# main.net
KiCad netlist of a schematic drawn in Altium Designer
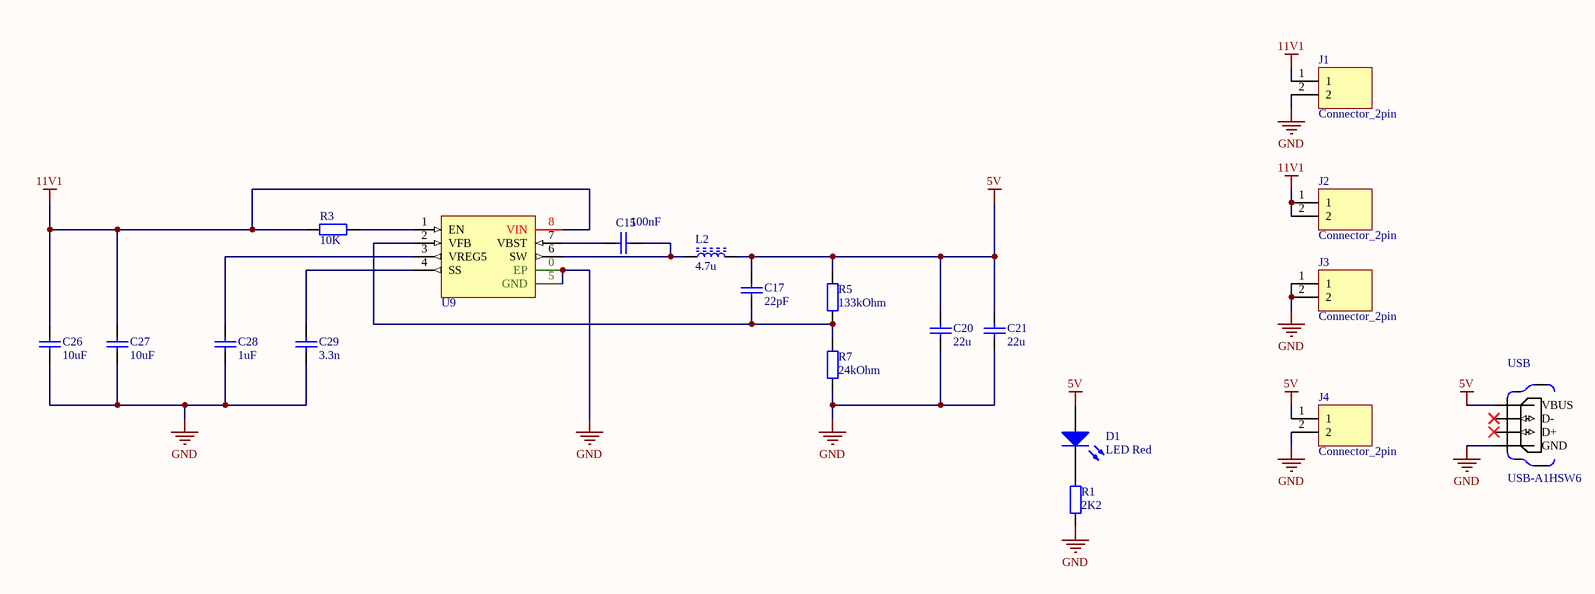
[diagram p0: main.SchDoc]

(export (version "E")
  (design (tool "Eeschema 10.0.6"))
  (components
    (comp (ref "C15")
      (value "100nF")
      (footprint "FP_0805_CAP_085")
      (description "Capacitor")
      (fields (field (name "TOLERANCE") "+80%/-20%") (field (name "VOLTAGE") "25V"))
      (libsource (lib "hallglib") (part "CAP 100nF"))
    )
    (comp (ref "C17")
      (value "22pF")
      (footprint "FP_0805_CAP_085")
      (description "Capacitor")
      (fields (field (name "TOLERANCE") "5%") (field (name "VOLTAGE") "50V"))
      (libsource (lib "hallglib") (part "CAP 22pF"))
    )
    (comp (ref "C20")
      (value "CL32A226KOJNNNE")
      (footprint "1210")
      (description "22uF 1210 10% 16V X5R CL32A226KOJNNNE (SAM) [ 82-08-05 ]")
      (fields (field (name "CAPACITANCE") "22u"))
      (libsource (lib "RobonAUT") (part "CL32A226KOJNNNE"))
    )
    (comp (ref "C21")
      (value "CL32A226KOJNNNE")
      (footprint "1210")
      (description "22uF 1210 10% 16V X5R CL32A226KOJNNNE (SAM) [ 82-08-05 ]")
      (fields (field (name "CAPACITANCE") "22u"))
      (libsource (lib "RobonAUT") (part "CL32A226KOJNNNE"))
    )
    (comp (ref "C26")
      (value "885012209005")
      (footprint "1210")
      (description "SMD Multilayer Ceramic Capacitor, 1210 [3225 Metric], 10 µF, 10 V, ± 10%, X7R, WCAP-CSGP Series")
      (fields (field (name "CAPACITANCE") "10uF"))
      (libsource (lib "RobonAUT") (part "885012209005"))
    )
    (comp (ref "C27")
      (value "885012209005")
      (footprint "1210")
      (description "SMD Multilayer Ceramic Capacitor, 1210 [3225 Metric], 10 µF, 10 V, ± 10%, X7R, WCAP-CSGP Series")
      (fields (field (name "CAPACITANCE") "10uF"))
      (libsource (lib "RobonAUT") (part "885012209005"))
    )
    (comp (ref "C28")
      (value "VJ0805Y105KXQTW1BC")
      (footprint "0805")
      (description "SMD Multilayer Ceramic Capacitor, 0805 [2012 Metric], 1 µF, 10 V, ± 10%, X7R, VJ Series")
      (fields (field (name "CAPACITANCE") "1uF"))
      (libsource (lib "RobonAUT") (part "VJ0805Y105KXQTW1BC"))
    )
    (comp (ref "C29")
      (value "CC0805JRNP08BN332")
      (footprint "0805")
      (description "3.3nF 0805 5% 25V NP0 CC0805JRNP08BN332 (YAG) [ 82-04-69 ]")
      (fields (field (name "CAPACITANCE") "3.3n"))
      (libsource (lib "RobonAUT") (part "CC0805JRNP08BN332"))
    )
    (comp (ref "D1")
      (value "LED Red")
      (footprint "FP_0805_LED_RED")
      (description "Red LED")
      (libsource (lib "hallglib") (part "LED Red"))
    )
    (comp (ref "J1")
      (value "Connector_2pin")
      (footprint "PT_2-5")
      (libsource (lib "mylib") (part "Connector_2pin"))
    )
    (comp (ref "J2")
      (value "Connector_2pin")
      (footprint "PT_2-5")
      (libsource (lib "mylib") (part "Connector_2pin"))
    )
    (comp (ref "J3")
      (value "Connector_2pin")
      (footprint "PT_2-5")
      (libsource (lib "mylib") (part "Connector_2pin"))
    )
    (comp (ref "J4")
      (value "Connector_2pin")
      (footprint "PT_2-5")
      (libsource (lib "mylib") (part "Connector_2pin"))
    )
    (comp (ref "L2")
      (value "VLS6045EX-4R7M")
      (footprint "TDK_IND_6045")
      (description "Power Inductor (SMD), 4.7 µH, 4.2 A, Wirewound, 5.8 A, VLS-EX Series, 6mm x 6mm x 4.5mm")
      (fields (field (name "INDUCTANCE") "4.7u"))
      (libsource (lib "RobonAUT") (part "VLS6045EX-4R7M"))
    )
    (comp (ref "R1")
      (value "2K2")
      (footprint "FP_0805_RES")
      (description "Resistor")
      (fields (field (name "TOLERANCE") "1%") (field (name "POWER") "125mW"))
      (libsource (lib "hallglib") (part "RES 2K2"))
    )
    (comp (ref "R3")
      (value "10K")
      (footprint "FP_0805_RES")
      (description "Resistor")
      (fields (field (name "TOLERANCE") "5%") (field (name "POWER") "125mW"))
      (libsource (lib "hallglib") (part "RES 10K"))
    )
    (comp (ref "R5")
      (value "CR0805-FX-1333ELF")
      (footprint "0805-W")
      (description "SMD Chip Resistor, 133kOhm, 0805")
      (fields (field (name "RESISTANCE") "133kOhm"))
      (libsource (lib "HomeProjects") (part "CR0805-FX-1333ELF"))
    )
    (comp (ref "R7")
      (value "CR0805-FX-2402ELF")
      (footprint "0805-W")
      (description "SMD Chip Resistor, 24kOhm, 0805")
      (fields (field (name "RESISTANCE") "24kOhm"))
      (libsource (lib "HomeProjects") (part "CR0805-FX-2402ELF"))
    )
    (comp (ref "U9")
      (value "TPS54227DDAR")
      (footprint "8-Pin HSOP with ThermalPad")
      (libsource (lib "RobonAUT") (part "TPS54227DDAR"))
    )
    (comp (ref "USB")
      (value "USB-A1HSW6")
      (footprint "*OST_USB-A1HSW6")
      (description "USB - A Receptacle Connector 4 Position Through Hole, Right Angle")
      (fields (field (name "MF") "On Shore"))
      (libsource (lib "USB-A1HSW6") (part "USB-A1HSW6"))
    )
  )
  (nets
    (net (code "1") (name "5V") (class "Default")
      (node (ref "C17") (pin "2") (pinfunction "2_2") (pintype "passive"))
      (node (ref "C20") (pin "2") (pinfunction "2_2") (pintype "passive"))
      (node (ref "C21") (pin "2") (pinfunction "2_2") (pintype "passive"))
      (node (ref "D1") (pin "1") (pinfunction "A_1") (pintype "passive"))
      (node (ref "J4") (pin "1") (pinfunction "1_1") (pintype "passive"))
      (node (ref "L2") (pin "2") (pinfunction "2_2") (pintype "passive"))
      (node (ref "R5") (pin "2") (pinfunction "2_2") (pintype "passive"))
      (node (ref "USB") (pin "1") (pinfunction "VBUS_1") (pintype "power_in"))
    )
    (net (code "2") (name "11V1") (class "Default")
      (node (ref "C26") (pin "2") (pinfunction "2_2") (pintype "passive"))
      (node (ref "C27") (pin "2") (pinfunction "2_2") (pintype "passive"))
      (node (ref "J1") (pin "1") (pinfunction "1_1") (pintype "passive"))
      (node (ref "J2") (pin "1") (pinfunction "1_1") (pintype "passive"))
      (node (ref "J2") (pin "2") (pinfunction "2_2") (pintype "passive"))
      (node (ref "R3") (pin "1") (pinfunction "1_1") (pintype "passive"))
      (node (ref "U9") (pin "8") (pinfunction "VIN_8") (pintype "power_in"))
    )
    (net (code "3") (name "GND") (class "Default")
      (node (ref "C20") (pin "1") (pinfunction "1_1") (pintype "passive"))
      (node (ref "C21") (pin "1") (pinfunction "1_1") (pintype "passive"))
      (node (ref "C26") (pin "1") (pinfunction "1_1") (pintype "passive"))
      (node (ref "C27") (pin "1") (pinfunction "1_1") (pintype "passive"))
      (node (ref "C28") (pin "1") (pinfunction "1_1") (pintype "passive"))
      (node (ref "C29") (pin "1") (pinfunction "1_1") (pintype "passive"))
      (node (ref "J1") (pin "2") (pinfunction "2_2") (pintype "passive"))
      (node (ref "J3") (pin "1") (pinfunction "1_1") (pintype "passive"))
      (node (ref "J3") (pin "2") (pinfunction "2_2") (pintype "passive"))
      (node (ref "J4") (pin "2") (pinfunction "2_2") (pintype "passive"))
      (node (ref "R1") (pin "1") (pinfunction "1_1") (pintype "passive"))
      (node (ref "R7") (pin "1") (pinfunction "1_1") (pintype "passive"))
      (node (ref "U9") (pin "0") (pinfunction "EP_0") (pintype "power_in"))
      (node (ref "U9") (pin "5") (pinfunction "GND_5") (pintype "power_in"))
      (node (ref "USB") (pin "4") (pinfunction "GND_4") (pintype "power_in"))
    )
    (net (code "4") (name "Net-(D1-K)") (class "Default")
      (node (ref "D1") (pin "2") (pinfunction "K_2") (pintype "passive"))
      (node (ref "R1") (pin "2") (pinfunction "2_2") (pintype "passive"))
    )
    (net (code "5") (name "Net-(U9-EN)") (class "Default")
      (node (ref "R3") (pin "2") (pinfunction "2_2") (pintype "passive"))
      (node (ref "U9") (pin "1") (pinfunction "EN_1") (pintype "input"))
    )
    (net (code "6") (name "Net-(U9-SS)") (class "Default")
      (node (ref "C29") (pin "2") (pinfunction "2_2") (pintype "passive"))
      (node (ref "U9") (pin "4") (pinfunction "SS_4") (pintype "output"))
    )
    (net (code "7") (name "Net-(U9-SW)") (class "Default")
      (node (ref "C15") (pin "2") (pinfunction "2_2") (pintype "passive"))
      (node (ref "L2") (pin "1") (pinfunction "1_1") (pintype "passive"))
      (node (ref "U9") (pin "6") (pinfunction "SW_6") (pintype "output"))
    )
    (net (code "8") (name "Net-(U9-VBST)") (class "Default")
      (node (ref "C15") (pin "1") (pinfunction "1_1") (pintype "passive"))
      (node (ref "U9") (pin "7") (pinfunction "VBST_7") (pintype "input"))
    )
    (net (code "9") (name "Net-(U9-VFB)") (class "Default")
      (node (ref "C17") (pin "1") (pinfunction "1_1") (pintype "passive"))
      (node (ref "R5") (pin "1") (pinfunction "1_1") (pintype "passive"))
      (node (ref "R7") (pin "2") (pinfunction "2_2") (pintype "passive"))
      (node (ref "U9") (pin "2") (pinfunction "VFB_2") (pintype "input"))
    )
    (net (code "10") (name "Net-(U9-VREG5)") (class "Default")
      (node (ref "C28") (pin "2") (pinfunction "2_2") (pintype "passive"))
      (node (ref "U9") (pin "3") (pinfunction "VREG5_3") (pintype "output"))
    )
    (net (code "11") (name "unconnected-(USB-D+-Pad3)") (class "Default")
      (node (ref "USB") (pin "3") (pinfunction "D+_3") (pintype "bidirectional+no_connect"))
    )
    (net (code "12") (name "unconnected-(USB-D--Pad2)") (class "Default")
      (node (ref "USB") (pin "2") (pinfunction "D-_2") (pintype "bidirectional+no_connect"))
    )
  )
)
